# 32u4_board.net
KiCad netlist of a schematic drawn in EAGLE
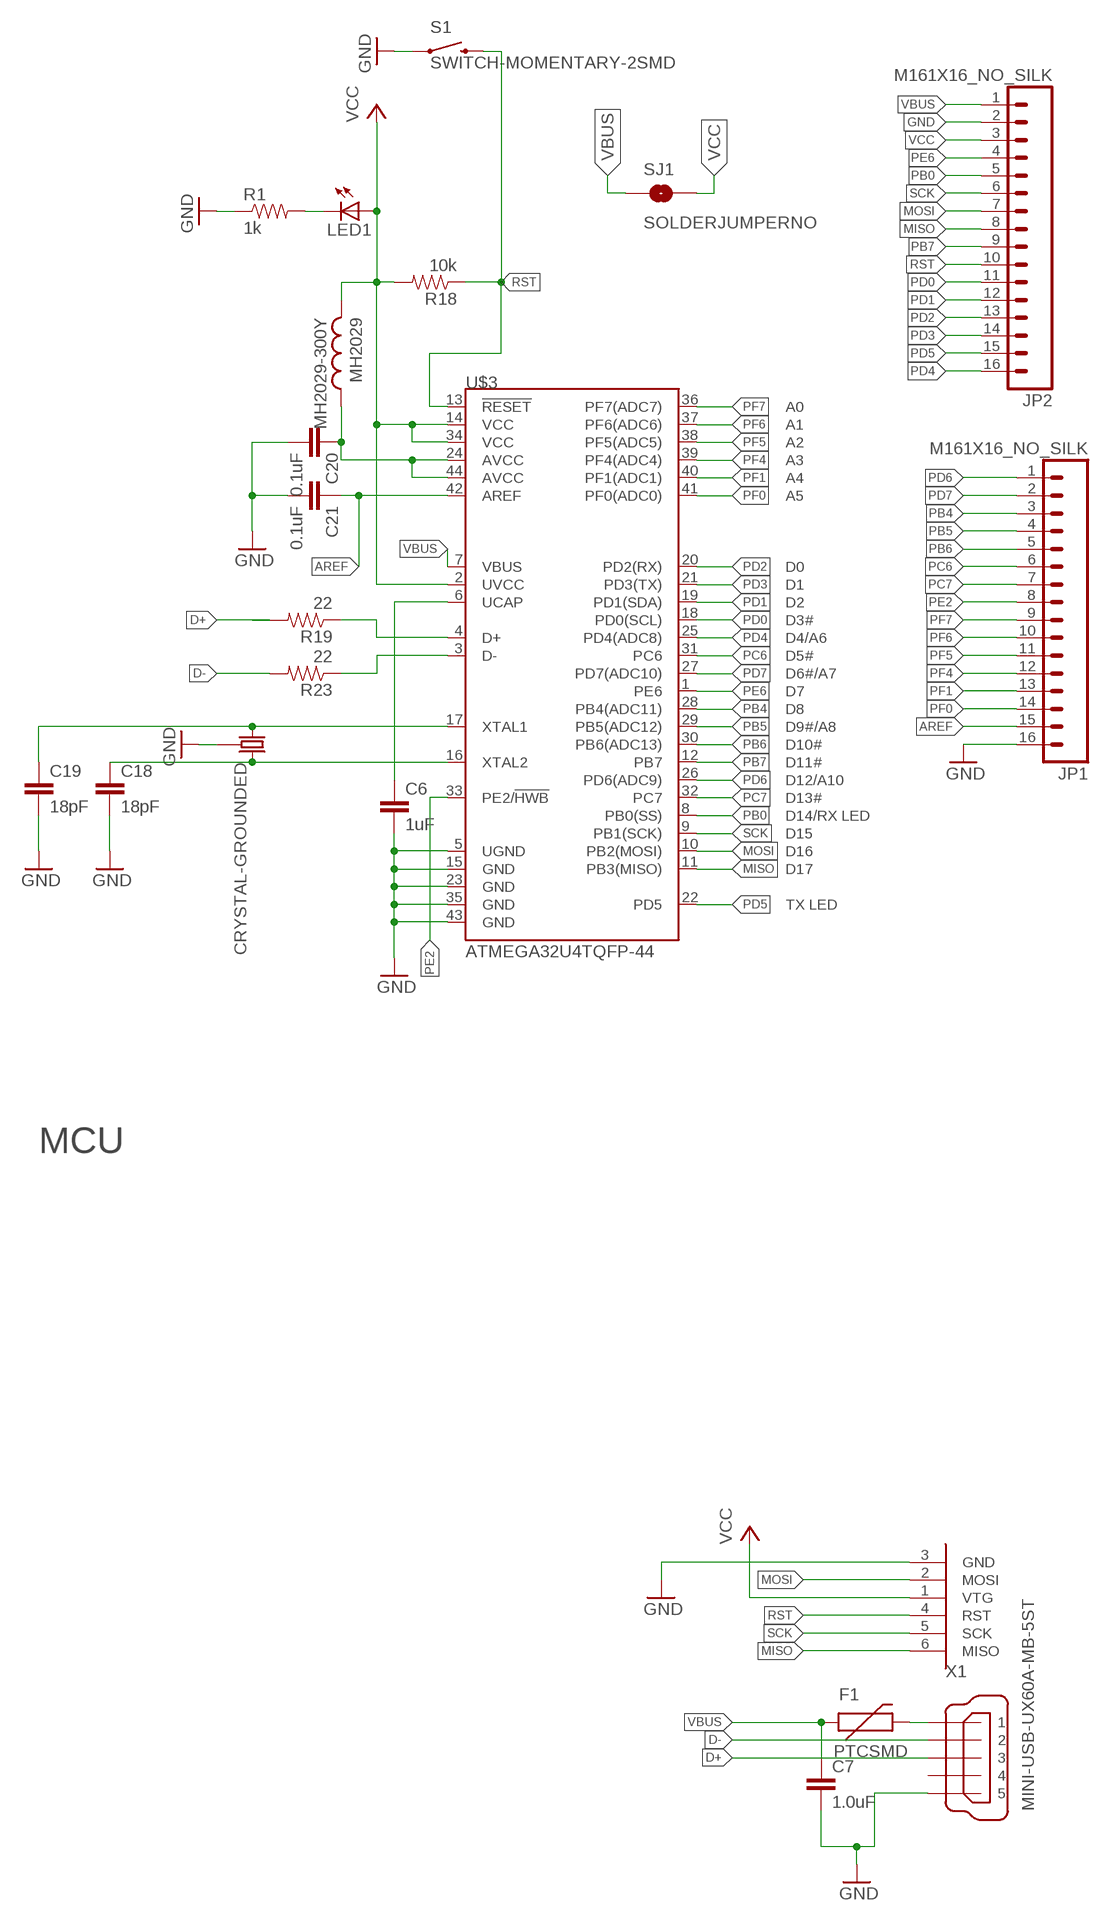
[diagram p0: schematic, sheet 1]

(export (version "E")
  (design (tool "Eeschema 10.0.6"))
  (components
    (comp (ref "C6")
      (value "1uF")
      (footprint "eagle-import:0603-CAP")
      (libsource (lib "eagle-import") (part "0.1UF-25V(+80/-20%)(0603)"))
    )
    (comp (ref "C7")
      (value "1.0uF")
      (footprint "eagle-import:0603-CAP")
      (libsource (lib "eagle-import") (part "1.0UF-16V-10%(0603)"))
    )
    (comp (ref "C18")
      (value "18pF")
      (footprint "eagle-import:0603-CAP")
      (libsource (lib "eagle-import") (part "0.1UF-25V(+80/-20%)(0603)"))
    )
    (comp (ref "C19")
      (value "18pF")
      (footprint "eagle-import:0603-CAP")
      (libsource (lib "eagle-import") (part "0.1UF-25V(+80/-20%)(0603)"))
    )
    (comp (ref "C20")
      (value "0.1uF")
      (footprint "eagle-import:0603-CAP")
      (libsource (lib "eagle-import") (part "0.1UF-25V(+80/-20%)(0603)"))
    )
    (comp (ref "C21")
      (value "0.1uF")
      (footprint "eagle-import:0603-CAP")
      (libsource (lib "eagle-import") (part "0.1UF-25V(+80/-20%)(0603)"))
    )
    (comp (ref "F1")
      (value "PTCSMD")
      (footprint "eagle-import:PTC-1206")
      (libsource (lib "eagle-import") (part "PTCSMD"))
    )
    (comp (ref "JP1")
      (value "M161X16_NO_SILK")
      (footprint "eagle-import:1X16_NO_SILK")
      (libsource (lib "eagle-import") (part "M161X16_NO_SILK"))
    )
    (comp (ref "JP2")
      (value "M161X16_NO_SILK")
      (footprint "eagle-import:1X16_NO_SILK")
      (libsource (lib "eagle-import") (part "M161X16_NO_SILK"))
    )
    (comp (ref "LED1")
      (value "LEDCHIPLED_0603")
      (footprint "eagle-import:CHIPLED_0603")
      (libsource (lib "eagle-import") (part "LEDCHIPLED_0603"))
    )
    (comp (ref "MH2029")
      (value "MH2029-300Y")
      (footprint "eagle-import:L2012C")
      (libsource (lib "eagle-import") (part "L-USL2012C"))
    )
    (comp (ref "R1")
      (value "1k")
      (footprint "eagle-import:0603-RES")
      (libsource (lib "eagle-import") (part "RESISTOR0603"))
    )
    (comp (ref "R18")
      (value "10k")
      (footprint "eagle-import:0603-RES")
      (libsource (lib "eagle-import") (part "RESISTOR0603-RES"))
    )
    (comp (ref "R19")
      (value "22")
      (footprint "eagle-import:0603-RES")
      (libsource (lib "eagle-import") (part "RESISTOR0603-RES"))
    )
    (comp (ref "R23")
      (value "22")
      (footprint "eagle-import:0603-RES")
      (libsource (lib "eagle-import") (part "RESISTOR0603-RES"))
    )
    (comp (ref "S1")
      (value "SWITCH-MOMENTARY-2SMD")
      (footprint "eagle-import:TACTILE_SWITCH_SMD")
      (libsource (lib "eagle-import") (part "SWITCH-MOMENTARY-2SMD"))
    )
    (comp (ref "SJ1")
      (value "SOLDERJUMPERNO")
      (footprint "eagle-import:SJ_2S-NO")
      (libsource (lib "eagle-import") (part "SOLDERJUMPERNO"))
    )
    (comp (ref "U$2")
      (value "ICSP_SMD")
      (footprint "eagle-import:ICSP")
      (libsource (lib "eagle-import") (part "ICSP_SMD"))
    )
    (comp (ref "U$3")
      (value "ATMEGA32U4TQFP-44")
      (footprint "eagle-import:TQFP44")
      (libsource (lib "eagle-import") (part "ATMEGA32U4TQFP-44"))
    )
    (comp (ref "U$4")
      (value "CRYSTAL-GROUNDED")
      (footprint "eagle-import:CRYSTAL-SMD-5X3")
      (libsource (lib "eagle-import") (part "CRYSTAL-GROUNDED"))
    )
    (comp (ref "X1")
      (value "MINI-USB-UX60A-MB-5ST")
      (footprint "eagle-import:UX60A-MB-5ST")
      (libsource (lib "eagle-import") (part "MINI-USB-UX60A-MB-5ST"))
    )
  )
  (nets
    (net (code "1") (name "AREF") (class "Default")
      (node (ref "C21") (pin "1") (pinfunction "1_1") (pintype "passive"))
      (node (ref "JP1") (pin "15") (pinfunction "15_15") (pintype "passive"))
      (node (ref "U$3") (pin "42") (pinfunction "AREF_42") (pintype "bidirectional"))
    )
    (net (code "2") (name "D+") (class "Default")
      (node (ref "R19") (pin "2") (pinfunction "2_2") (pintype "passive"))
      (node (ref "X1") (pin "3") (pinfunction "3_3") (pintype "input"))
    )
    (net (code "3") (name "D-") (class "Default")
      (node (ref "R23") (pin "2") (pinfunction "2_2") (pintype "passive"))
      (node (ref "X1") (pin "2") (pinfunction "2_2") (pintype "input"))
    )
    (net (code "4") (name "GND") (class "Default")
      (node (ref "C18") (pin "2") (pinfunction "2_2") (pintype "passive"))
      (node (ref "C19") (pin "2") (pinfunction "2_2") (pintype "passive"))
      (node (ref "C20") (pin "2") (pinfunction "2_2") (pintype "passive"))
      (node (ref "C21") (pin "2") (pinfunction "2_2") (pintype "passive"))
      (node (ref "C6") (pin "2") (pinfunction "2_2") (pintype "passive"))
      (node (ref "C7") (pin "2") (pinfunction "2_2") (pintype "passive"))
      (node (ref "JP1") (pin "16") (pinfunction "16_16") (pintype "passive"))
      (node (ref "JP2") (pin "2") (pinfunction "2_2") (pintype "passive"))
      (node (ref "R1") (pin "1") (pinfunction "1_1") (pintype "passive"))
      (node (ref "S1") (pin "1") (pinfunction "1_1") (pintype "passive"))
      (node (ref "U$2") (pin "3") (pinfunction "GND_3") (pintype "bidirectional"))
      (node (ref "U$3") (pin "15") (pinfunction "GND_15") (pintype "bidirectional"))
      (node (ref "U$3") (pin "23") (pinfunction "GND_23") (pintype "bidirectional"))
      (node (ref "U$3") (pin "35") (pinfunction "GND_35") (pintype "bidirectional"))
      (node (ref "U$3") (pin "43") (pinfunction "GND_43") (pintype "bidirectional"))
      (node (ref "U$3") (pin "5") (pinfunction "UGND_5") (pintype "bidirectional"))
      (node (ref "U$4") (pin "2") (pinfunction "3_2") (pintype "passive"))
      (node (ref "U$4") (pin "4") (pinfunction "3_4") (pintype "passive"))
      (node (ref "X1") (pin "5") (pinfunction "5_5") (pintype "input"))
    )
    (net (code "5") (name "MISO") (class "Default")
      (node (ref "JP2") (pin "8") (pinfunction "8_8") (pintype "passive"))
      (node (ref "U$2") (pin "6") (pinfunction "MISO_6") (pintype "bidirectional"))
      (node (ref "U$3") (pin "11") (pinfunction "PB3(MISO)_11") (pintype "bidirectional"))
    )
    (net (code "6") (name "MOSI") (class "Default")
      (node (ref "JP2") (pin "7") (pinfunction "7_7") (pintype "passive"))
      (node (ref "U$2") (pin "2") (pinfunction "MOSI_2") (pintype "bidirectional"))
      (node (ref "U$3") (pin "10") (pinfunction "PB2(MOSI)_10") (pintype "bidirectional"))
    )
    (net (code "7") (name "Net-(C20-Pad1)") (class "Default")
      (node (ref "C20") (pin "1") (pinfunction "1_1") (pintype "passive"))
      (node (ref "MH2029") (pin "1") (pinfunction "1_1") (pintype "passive"))
      (node (ref "U$3") (pin "24") (pinfunction "AVCC_24") (pintype "bidirectional"))
      (node (ref "U$3") (pin "44") (pinfunction "AVCC_44") (pintype "bidirectional"))
    )
    (net (code "8") (name "Net-(F1-Pad2)") (class "Default")
      (node (ref "F1") (pin "2") (pinfunction "2_2") (pintype "bidirectional"))
      (node (ref "X1") (pin "1") (pinfunction "1_1") (pintype "input"))
    )
    (net (code "9") (name "Net-(LED1-PadC)") (class "Default")
      (node (ref "LED1") (pin "C") (pinfunction "C_C") (pintype "passive"))
      (node (ref "R1") (pin "2") (pinfunction "2_2") (pintype "passive"))
    )
    (net (code "10") (name "Net-(U$3-D+)") (class "Default")
      (node (ref "R19") (pin "1") (pinfunction "1_1") (pintype "passive"))
      (node (ref "U$3") (pin "4") (pinfunction "D+_4") (pintype "bidirectional"))
    )
    (net (code "11") (name "Net-(U$3-D-)") (class "Default")
      (node (ref "R23") (pin "1") (pinfunction "1_1") (pintype "passive"))
      (node (ref "U$3") (pin "3") (pinfunction "D-_3") (pintype "bidirectional"))
    )
    (net (code "12") (name "Net-(U$3-UCAP)") (class "Default")
      (node (ref "C6") (pin "1") (pinfunction "1_1") (pintype "passive"))
      (node (ref "U$3") (pin "6") (pinfunction "UCAP_6") (pintype "bidirectional"))
    )
    (net (code "13") (name "Net-(U$3-XTAL1)") (class "Default")
      (node (ref "C19") (pin "1") (pinfunction "1_1") (pintype "passive"))
      (node (ref "U$3") (pin "17") (pinfunction "XTAL1_17") (pintype "bidirectional"))
      (node (ref "U$4") (pin "3") (pinfunction "1_3") (pintype "passive"))
    )
    (net (code "14") (name "Net-(U$3-XTAL2)") (class "Default")
      (node (ref "C18") (pin "1") (pinfunction "1_1") (pintype "passive"))
      (node (ref "U$3") (pin "16") (pinfunction "XTAL2_16") (pintype "bidirectional"))
      (node (ref "U$4") (pin "1") (pinfunction "2_1") (pintype "passive"))
    )
    (net (code "15") (name "PB0") (class "Default")
      (node (ref "JP2") (pin "5") (pinfunction "5_5") (pintype "passive"))
      (node (ref "U$3") (pin "8") (pinfunction "PB0(SS)_8") (pintype "bidirectional"))
    )
    (net (code "16") (name "PB4") (class "Default")
      (node (ref "JP1") (pin "3") (pinfunction "3_3") (pintype "passive"))
      (node (ref "U$3") (pin "28") (pinfunction "PB4(ADC11)_28") (pintype "bidirectional"))
    )
    (net (code "17") (name "PB5") (class "Default")
      (node (ref "JP1") (pin "4") (pinfunction "4_4") (pintype "passive"))
      (node (ref "U$3") (pin "29") (pinfunction "PB5(ADC12)_29") (pintype "bidirectional"))
    )
    (net (code "18") (name "PB6") (class "Default")
      (node (ref "JP1") (pin "5") (pinfunction "5_5") (pintype "passive"))
      (node (ref "U$3") (pin "30") (pinfunction "PB6(ADC13)_30") (pintype "bidirectional"))
    )
    (net (code "19") (name "PB7") (class "Default")
      (node (ref "JP2") (pin "9") (pinfunction "9_9") (pintype "passive"))
      (node (ref "U$3") (pin "12") (pinfunction "PB7_12") (pintype "bidirectional"))
    )
    (net (code "20") (name "PC6") (class "Default")
      (node (ref "JP1") (pin "6") (pinfunction "6_6") (pintype "passive"))
      (node (ref "U$3") (pin "31") (pinfunction "PC6_31") (pintype "bidirectional"))
    )
    (net (code "21") (name "PC7") (class "Default")
      (node (ref "JP1") (pin "7") (pinfunction "7_7") (pintype "passive"))
      (node (ref "U$3") (pin "32") (pinfunction "PC7_32") (pintype "bidirectional"))
    )
    (net (code "22") (name "PD0") (class "Default")
      (node (ref "JP2") (pin "11") (pinfunction "11_11") (pintype "passive"))
      (node (ref "U$3") (pin "18") (pinfunction "PD0(SCL)_18") (pintype "bidirectional"))
    )
    (net (code "23") (name "PD1") (class "Default")
      (node (ref "JP2") (pin "12") (pinfunction "12_12") (pintype "passive"))
      (node (ref "U$3") (pin "19") (pinfunction "PD1(SDA)_19") (pintype "bidirectional"))
    )
    (net (code "24") (name "PD2") (class "Default")
      (node (ref "JP2") (pin "13") (pinfunction "13_13") (pintype "passive"))
      (node (ref "U$3") (pin "20") (pinfunction "PD2(RX)_20") (pintype "bidirectional"))
    )
    (net (code "25") (name "PD3") (class "Default")
      (node (ref "JP2") (pin "14") (pinfunction "14_14") (pintype "passive"))
      (node (ref "U$3") (pin "21") (pinfunction "PD3(TX)_21") (pintype "bidirectional"))
    )
    (net (code "26") (name "PD4") (class "Default")
      (node (ref "JP2") (pin "16") (pinfunction "16_16") (pintype "passive"))
      (node (ref "U$3") (pin "25") (pinfunction "PD4(ADC8)_25") (pintype "bidirectional"))
    )
    (net (code "27") (name "PD5") (class "Default")
      (node (ref "JP2") (pin "15") (pinfunction "15_15") (pintype "passive"))
      (node (ref "U$3") (pin "22") (pinfunction "PD5_22") (pintype "bidirectional"))
    )
    (net (code "28") (name "PD6") (class "Default")
      (node (ref "JP1") (pin "1") (pinfunction "1_1") (pintype "passive"))
      (node (ref "U$3") (pin "26") (pinfunction "PD6(ADC9)_26") (pintype "bidirectional"))
    )
    (net (code "29") (name "PD7") (class "Default")
      (node (ref "JP1") (pin "2") (pinfunction "2_2") (pintype "passive"))
      (node (ref "U$3") (pin "27") (pinfunction "PD7(ADC10)_27") (pintype "bidirectional"))
    )
    (net (code "30") (name "PE2") (class "Default")
      (node (ref "JP1") (pin "8") (pinfunction "8_8") (pintype "passive"))
      (node (ref "U$3") (pin "33") (pinfunction "PE2/~{HWB}_33") (pintype "bidirectional"))
    )
    (net (code "31") (name "PE6") (class "Default")
      (node (ref "JP2") (pin "4") (pinfunction "4_4") (pintype "passive"))
      (node (ref "U$3") (pin "1") (pinfunction "PE6_1") (pintype "bidirectional"))
    )
    (net (code "32") (name "PF0") (class "Default")
      (node (ref "JP1") (pin "14") (pinfunction "14_14") (pintype "passive"))
      (node (ref "U$3") (pin "41") (pinfunction "PF0(ADC0)_41") (pintype "bidirectional"))
    )
    (net (code "33") (name "PF1") (class "Default")
      (node (ref "JP1") (pin "13") (pinfunction "13_13") (pintype "passive"))
      (node (ref "U$3") (pin "40") (pinfunction "PF1(ADC1)_40") (pintype "bidirectional"))
    )
    (net (code "34") (name "PF4") (class "Default")
      (node (ref "JP1") (pin "12") (pinfunction "12_12") (pintype "passive"))
      (node (ref "U$3") (pin "39") (pinfunction "PF4(ADC4)_39") (pintype "bidirectional"))
    )
    (net (code "35") (name "PF5") (class "Default")
      (node (ref "JP1") (pin "11") (pinfunction "11_11") (pintype "passive"))
      (node (ref "U$3") (pin "38") (pinfunction "PF5(ADC5)_38") (pintype "bidirectional"))
    )
    (net (code "36") (name "PF6") (class "Default")
      (node (ref "JP1") (pin "10") (pinfunction "10_10") (pintype "passive"))
      (node (ref "U$3") (pin "37") (pinfunction "PF6(ADC6)_37") (pintype "bidirectional"))
    )
    (net (code "37") (name "PF7") (class "Default")
      (node (ref "JP1") (pin "9") (pinfunction "9_9") (pintype "passive"))
      (node (ref "U$3") (pin "36") (pinfunction "PF7(ADC7)_36") (pintype "bidirectional"))
    )
    (net (code "38") (name "RST") (class "Default")
      (node (ref "JP2") (pin "10") (pinfunction "10_10") (pintype "passive"))
      (node (ref "R18") (pin "1") (pinfunction "1_1") (pintype "passive"))
      (node (ref "S1") (pin "3") (pinfunction "2_3") (pintype "passive"))
      (node (ref "U$2") (pin "4") (pinfunction "RST_4") (pintype "bidirectional"))
      (node (ref "U$3") (pin "13") (pinfunction "~{RESET}_13") (pintype "bidirectional"))
    )
    (net (code "39") (name "SCK") (class "Default")
      (node (ref "JP2") (pin "6") (pinfunction "6_6") (pintype "passive"))
      (node (ref "U$2") (pin "5") (pinfunction "SCK_5") (pintype "bidirectional"))
      (node (ref "U$3") (pin "9") (pinfunction "PB1(SCK)_9") (pintype "bidirectional"))
    )
    (net (code "40") (name "VBUS") (class "Default")
      (node (ref "C7") (pin "1") (pinfunction "1_1") (pintype "passive"))
      (node (ref "F1") (pin "1") (pinfunction "1_1") (pintype "bidirectional"))
      (node (ref "JP2") (pin "1") (pinfunction "1_1") (pintype "passive"))
      (node (ref "SJ1") (pin "1") (pinfunction "1_1") (pintype "passive"))
      (node (ref "U$3") (pin "7") (pinfunction "VBUS_7") (pintype "bidirectional"))
    )
    (net (code "41") (name "VCC") (class "Default")
      (node (ref "JP2") (pin "3") (pinfunction "3_3") (pintype "passive"))
      (node (ref "LED1") (pin "A") (pinfunction "A_A") (pintype "passive"))
      (node (ref "MH2029") (pin "2") (pinfunction "2_2") (pintype "passive"))
      (node (ref "R18") (pin "2") (pinfunction "2_2") (pintype "passive"))
      (node (ref "SJ1") (pin "2") (pinfunction "2_2") (pintype "passive"))
      (node (ref "U$2") (pin "1") (pinfunction "VTG_1") (pintype "bidirectional"))
      (node (ref "U$3") (pin "14") (pinfunction "VCC_14") (pintype "bidirectional"))
      (node (ref "U$3") (pin "2") (pinfunction "UVCC_2") (pintype "bidirectional"))
      (node (ref "U$3") (pin "34") (pinfunction "VCC_34") (pintype "bidirectional"))
    )
    (net (code "42") (name "unconnected-(X1-Pad4)") (class "Default")
      (node (ref "X1") (pin "4") (pinfunction "4_4") (pintype "input"))
    )
  )
)
